# 85VAC_265VAC_6W_5V_SMPS_FLAYBACK.net
KiCad netlist of a schematic drawn in Altium Designer
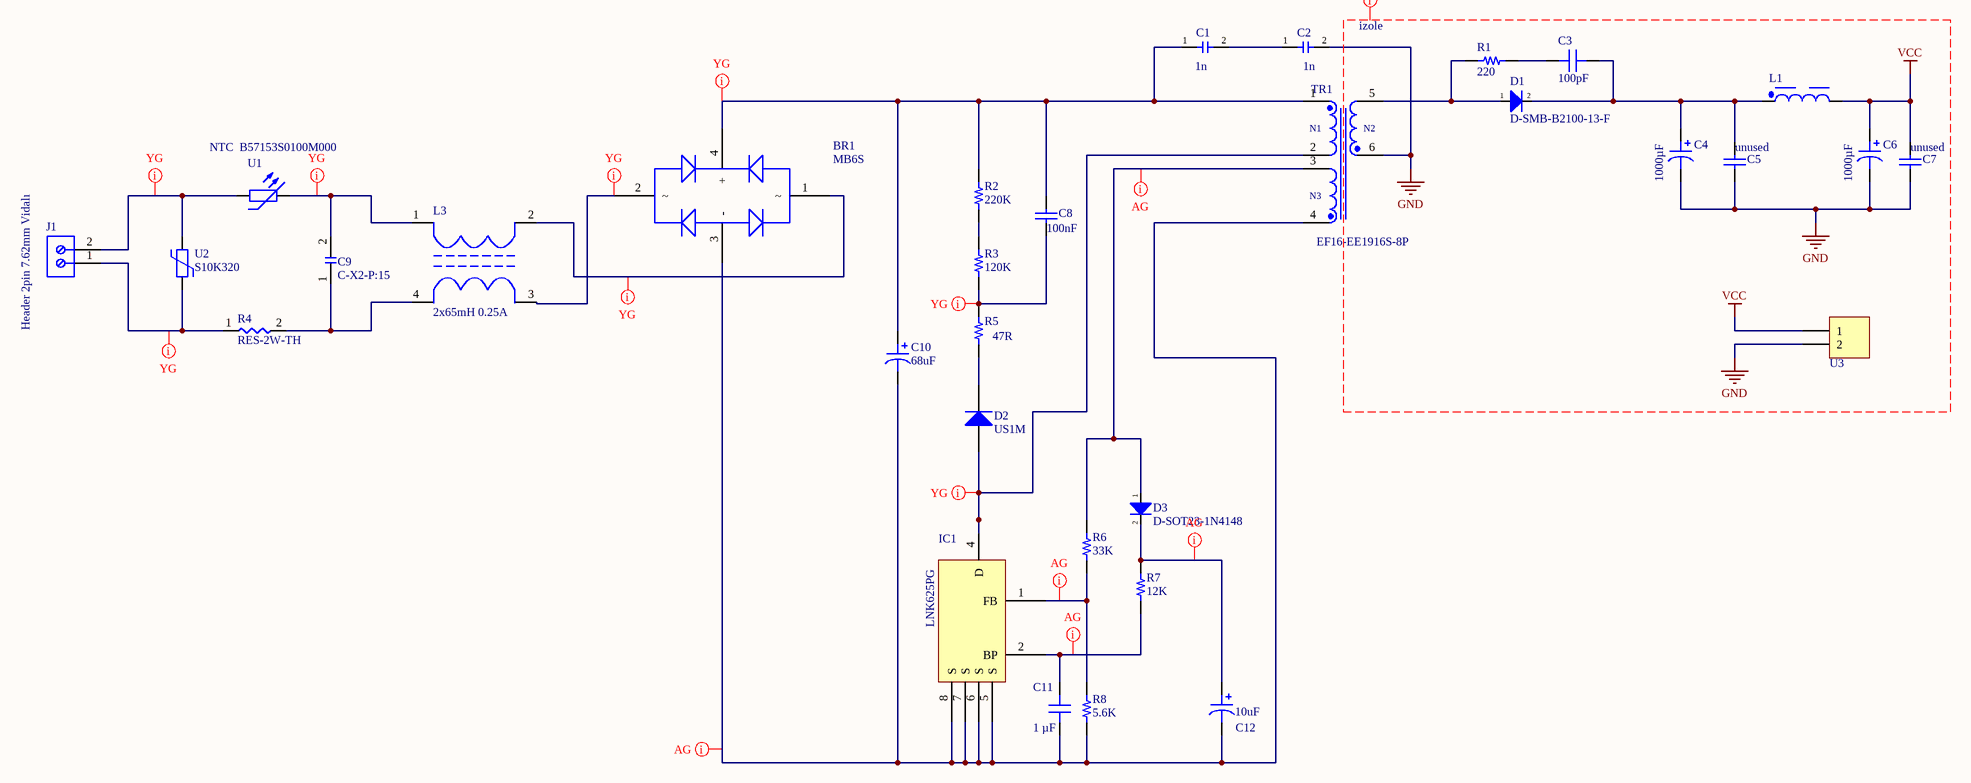
[diagram p0: 85VAC 265VAC 6W 5V SMPS FLAYBACK.SchDoc]

(export (version "E")
  (design (tool "Eeschema 10.0.6"))
  (components
    (comp (ref "BR1")
      (value "MB6S")
      (footprint "AltiumLive:TO269AA")
      (libsource (lib "AltiumLive") (part "MB6S"))
    )
    (comp (ref "C1")
      (value "1n")
      (footprint "AltiumLive:C-Y1-P:10")
      (libsource (lib "AltiumLive") (part "C-Y1-P{colon}10"))
    )
    (comp (ref "C2")
      (value "1n")
      (footprint "AltiumLive:C-Y1-P:10")
      (libsource (lib "AltiumLive") (part "C-Y1-P{colon}10"))
    )
    (comp (ref "C3")
      (value "100pF")
      (footprint "CAP 1206_3216 - 0.8MM")
      (description "CAP CER 1UF 25V X7R 1206")
      (fields (field (name "PART NUMBER") "CC1206KKX7R8BB105"))
      (libsource (lib "Celestial Altium Library - altium_library") (part "Capacitor"))
    )
    (comp (ref "C4")
      (value "~")
      (footprint "CAP TH ALUM ELEC D5.00mm S2.00mm H11.00mm")
      (description "CAP ALUM 1000UF 20% 25V RADIAL")
      (fields
        (field (name "PART NUMBER") "UKT1E4R7MDD")
        (field (name "CAPACITANCE") "1000µF")
        (field (name "MANUFACTURER") "Nichicon")
      )
      (libsource (lib "Celestial Altium Library - altium_library") (part "Polarised Capacitor"))
    )
    (comp (ref "C5")
      (value "unused")
      (footprint "WCAP-CSGP_1206_L3.2W1.6H0.8")
      (description "WCAP-CSGP Multilayer Ceramic Chip Capacitor, General Purpose, size 1206, NP0, 1nF, 25VDC")
      (fields
        (field (name "MANUFACTURER PART NUMBER") "885012008026")
        (field (name "MANUFACTURER") "Wurth Elektronik")
      )
      (libsource (lib "WE - Passive Components") (part "Capacitor_Non-Polarized"))
    )
    (comp (ref "C6")
      (value "~")
      (footprint "CAP TH ALUM ELEC D5.00mm S2.00mm H11.00mm")
      (description "CAP ALUM 1000UF 20% 25V RADIAL")
      (fields
        (field (name "PART NUMBER") "UKT1E4R7MDD")
        (field (name "CAPACITANCE") "1000µF")
        (field (name "MANUFACTURER") "Nichicon")
      )
      (libsource (lib "Celestial Altium Library - altium_library") (part "Polarised Capacitor"))
    )
    (comp (ref "C7")
      (value "unused")
      (footprint "WCAP-CSGP_1206_L3.2W1.6H0.8")
      (description "WCAP-CSGP Multilayer Ceramic Chip Capacitor, General Purpose, size 1206, NP0, 1nF, 25VDC")
      (fields
        (field (name "MANUFACTURER PART NUMBER") "885012008026")
        (field (name "MANUFACTURER") "Wurth Elektronik")
      )
      (libsource (lib "WE - Passive Components") (part "Capacitor_Non-Polarized"))
    )
    (comp (ref "C8")
      (value "100nF")
      (footprint "RCE7U2J333J5B1H03B")
      (description "490-8944-ND")
      (fields (field (name "PUBLISHER") "Altium Limited"))
      (libsource (lib "FlybackKutuphane") (part "C Seramik 100nF 1kV X7R 5mm"))
    )
    (comp (ref "C9")
      (value "C-X2-P:15")
      (footprint "AltiumLive:C-X2-P:15")
      (description "CAP-X2-R15-17.5x7.5")
      (libsource (lib "AltiumLive") (part "C-X2-P{colon}15"))
    )
    (comp (ref "C10")
      (value "68uF")
      (footprint "CAP TH ALUM ELEC D18.00mm S7.50mm H42.00mm")
      (description "CAP ALUM 68UF 20% 450V RADIAL")
      (fields (field (name "PART NUMBER") "EEU-EE2W680"))
      (libsource (lib "Celestial Altium Library - altium_library") (part "Polarised Capacitor"))
    )
    (comp (ref "C11")
      (value "1 µF")
      (footprint "CAP 1206_3216 - 0.8MM")
      (description "CAP CER 1UF 25V X7R 1206")
      (fields (field (name "PART NUMBER") "CC1206KKX7R8BB105"))
      (libsource (lib "Celestial Altium Library - altium_library") (part "Capacitor"))
    )
    (comp (ref "C12")
      (value "10uF")
      (footprint "CAP TH ALUM ELEC D6.30mm S2.50mm H6.00mm")
      (description "CAP ALUM 10UF 20% 50V RADIAL")
      (fields (field (name "PART NUMBER") "UMA1H100MDD"))
      (libsource (lib "Celestial Altium Library - altium_library") (part "Polarised Capacitor"))
    )
    (comp (ref "D1")
      (value "D-SMB-B2100-13-F")
      (footprint "AltiumLive:D-SMB-B2100-13-F")
      (libsource (lib "AltiumLive") (part "D-SMB-B2100-13-F"))
    )
    (comp (ref "D2")
      (value "US1M")
      (footprint "DO-214AA(SMB)")
      (description "SMA")
      (libsource (lib "FlybackKutuphane") (part "US1M"))
    )
    (comp (ref "D3")
      (value "D-SOT23-1N4148")
      (footprint "AltiumLive:SOT23-3")
      (libsource (lib "AltiumLive") (part "D-SOT23-1N4148"))
    )
    (comp (ref "IC1")
      (value "LNK625PG")
      (footprint "Altiumlive:PDIP-8C")
      (libsource (lib "AltiumLive") (part "LNK625PG"))
    )
    (comp (ref "J1")
      (value "Header 2pin 7.62mm Vidalı")
      (footprint "Header 2 Pin 7.62mm Vidalı")
      (description "691214410002")
      (fields (field (name "PART NUMBER") "691218410002") (field (name "PUBLISHER") "Wurth Elektronik"))
      (libsource (lib "FlybackKutuphane") (part "Header 2pin 7.62mm Vidalı"))
    )
    (comp (ref "L1")
      (value "1000uH, 0.25A")
      (footprint "WE-TI_5075")
      (description "WE-TI Radial Leaded Wire Wound Inductor, size 5075, 1000uH, 0.25A, 6Ohm")
      (fields
        (field (name "MANUFACTURER PART NUMBER") "7447462102")
        (field (name "MANUFACTURER") "Wurth Elektronik")
      )
      (libsource (lib "WE - Passive Components") (part "Inductor - 2"))
    )
    (comp (ref "L3")
      (value "2x65mH 0.25A")
      (footprint "AltiumLive:RN030923")
      (description "Line Filter RN030923")
      (libsource (lib "AltiumLive") (part "2x65mH 0.25A"))
    )
    (comp (ref "R1")
      (value "220")
      (footprint "RES 1206_3216")
      (description "RES 120K OHM 5% 1/4W 1206")
      (fields (field (name "PART NUMBER") "RMCF1206JT120K"))
      (libsource (lib "Celestial Altium Library - altium_library") (part "Resistor"))
    )
    (comp (ref "R2")
      (value "220K")
      (footprint "RES 1206_3216")
      (description "RES SMD 220K OHM 0.1% 1/4W 1206")
      (fields (field (name "PART NUMBER") "RT1206BRD07220KL"))
      (libsource (lib "Celestial Altium Library - altium_library") (part "Resistor"))
    )
    (comp (ref "R3")
      (value "120K")
      (footprint "RES 1206_3216")
      (description "RES 120K OHM 5% 1/4W 1206")
      (fields (field (name "PART NUMBER") "RMCF1206JT120K"))
      (libsource (lib "Celestial Altium Library - altium_library") (part "Resistor"))
    )
    (comp (ref "R4")
      (value "RES-2W-TH")
      (footprint "AltiumLive:RES-2W-TH")
      (libsource (lib "AltiumLive") (part "RES-2W-TH"))
    )
    (comp (ref "R5")
      (value "47R")
      (footprint "RES 1206_3216")
      (description "RES SMD 47 OHM 5% 1/4W 1206")
      (fields (field (name "PART NUMBER") "AC1206JR-0747RL"))
      (libsource (lib "Celestial Altium Library - altium_library") (part "Resistor"))
    )
    (comp (ref "R6")
      (value "33K")
      (footprint "RES 1206_3216")
      (description "RES 120K OHM 5% 1/4W 1206")
      (fields (field (name "PART NUMBER") "RMCF1206JT120K"))
      (libsource (lib "Celestial Altium Library - altium_library") (part "Resistor"))
    )
    (comp (ref "R7")
      (value "12K")
      (footprint "RES 1206_3216")
      (description "RES 12K OHM 5% 1/4W 1206")
      (fields (field (name "PART NUMBER") "RMCF1206JT120K"))
      (libsource (lib "Celestial Altium Library - altium_library") (part "Resistor"))
    )
    (comp (ref "R8")
      (value "5.6K")
      (footprint "RES 1206_3216")
      (description "RES 5.6K OHM 5% 1/4W 1206")
      (fields (field (name "PART NUMBER") "RMCF1206JT120K"))
      (libsource (lib "Celestial Altium Library - altium_library") (part "Resistor"))
    )
    (comp (ref "TR1")
      (value "EF16-EE1916S-8P")
      (footprint "AltiumLive:EF16-EE1916S-8P")
      (libsource (lib "AltiumLive") (part "EF16-EE1916S-8P"))
    )
    (comp (ref "U1")
      (value "NTC  B57153S0100M000")
      (footprint "NTC B57153S0100")
      (description "495-2076-ND")
      (fields (field (name "PUBLISHER") "Altium Limited"))
      (libsource (lib "FlybackKutuphane") (part "NTC 10R 2A 8.5mm"))
    )
    (comp (ref "U2")
      (value "S10K320")
      (footprint "Varistor630V")
      (fields (field (name "PUBLISHER") "Altium Limited"))
      (libsource (lib "FlybackKutuphane") (part "Varistor S10K320"))
    )
    (comp (ref "U3")
      (value "Terminal Blok 2 Pin 2.54mm")
      (footprint "Header 2pin 2.54mm Vidalı")
      (description "691210910002")
      (fields (field (name "PUBLISHER") "Altium Limited"))
      (libsource (lib "FlybackKutuphane") (part "Header 2 Pin 2.54mm Vidalı"))
    )
  )
  (nets
    (net (code "1") (name "GND") (class "Default")
      (node (ref "C2") (pin "2") (pintype "passive"))
      (node (ref "C4") (pin "2") (pinfunction "2_2") (pintype "passive"))
      (node (ref "C5") (pin "1") (pinfunction "1_1") (pintype "passive"))
      (node (ref "C6") (pin "2") (pinfunction "2_2") (pintype "passive"))
      (node (ref "C7") (pin "1") (pinfunction "1_1") (pintype "passive"))
      (node (ref "TR1") (pin "6") (pintype "passive"))
      (node (ref "U3") (pin "2") (pinfunction "2_2") (pintype "passive"))
    )
    (net (code "2") (name "Net-(BR1-+)") (class "Default")
      (node (ref "BR1") (pin "4") (pinfunction "+_4") (pintype "passive"))
      (node (ref "C1") (pin "1") (pintype "passive"))
      (node (ref "C10") (pin "1") (pinfunction "1_1") (pintype "passive"))
      (node (ref "C8") (pin "2") (pinfunction "2_2") (pintype "passive"))
      (node (ref "R2") (pin "2") (pinfunction "2_2") (pintype "passive"))
      (node (ref "TR1") (pin "1") (pintype "passive"))
    )
    (net (code "3") (name "Net-(BR1--)") (class "Default")
      (node (ref "BR1") (pin "3") (pinfunction "-_3") (pintype "passive"))
      (node (ref "C10") (pin "2") (pinfunction "2_2") (pintype "passive"))
      (node (ref "C11") (pin "1") (pinfunction "1_1") (pintype "passive"))
      (node (ref "C12") (pin "2") (pinfunction "2_2") (pintype "passive"))
      (node (ref "IC1") (pin "5") (pinfunction "S_5") (pintype "passive"))
      (node (ref "IC1") (pin "6") (pinfunction "S_6") (pintype "passive"))
      (node (ref "IC1") (pin "7") (pinfunction "S_7") (pintype "passive"))
      (node (ref "IC1") (pin "8") (pinfunction "S_8") (pintype "passive"))
      (node (ref "R8") (pin "1") (pinfunction "1_1") (pintype "passive"))
      (node (ref "TR1") (pin "4") (pintype "passive"))
    )
    (net (code "4") (name "Net-(BR1-~-Pad1)") (class "Default")
      (node (ref "BR1") (pin "1") (pinfunction "~_1") (pintype "passive"))
      (node (ref "L3") (pin "2") (pintype "passive"))
    )
    (net (code "5") (name "Net-(BR1-~-Pad2)") (class "Default")
      (node (ref "BR1") (pin "2") (pinfunction "~_2") (pintype "passive"))
      (node (ref "L3") (pin "3") (pintype "passive"))
    )
    (net (code "6") (name "Net-(C1-Pad2)") (class "Default")
      (node (ref "C1") (pin "2") (pintype "passive"))
      (node (ref "C2") (pin "1") (pintype "passive"))
    )
    (net (code "7") (name "Net-(C3-Pad1)") (class "Default")
      (node (ref "C3") (pin "1") (pinfunction "1_1") (pintype "passive"))
      (node (ref "C4") (pin "1") (pinfunction "1_1") (pintype "passive"))
      (node (ref "C5") (pin "2") (pinfunction "2_2") (pintype "passive"))
      (node (ref "D1") (pin "2") (pinfunction "A_2") (pintype "passive"))
      (node (ref "L1") (pin "1") (pinfunction "1_1") (pintype "passive"))
    )
    (net (code "8") (name "Net-(C3-Pad2)") (class "Default")
      (node (ref "C3") (pin "2") (pinfunction "2_2") (pintype "passive"))
      (node (ref "R1") (pin "1") (pinfunction "1_1") (pintype "passive"))
    )
    (net (code "9") (name "Net-(C8-Pad1)") (class "Default")
      (node (ref "C8") (pin "1") (pinfunction "1_1") (pintype "passive"))
      (node (ref "R3") (pin "1") (pinfunction "1_1") (pintype "passive"))
      (node (ref "R5") (pin "2") (pinfunction "2_2") (pintype "passive"))
    )
    (net (code "10") (name "Net-(C9-Pad1)") (class "Default")
      (node (ref "C9") (pin "1") (pintype "passive"))
      (node (ref "L3") (pin "4") (pintype "passive"))
      (node (ref "R4") (pin "2") (pintype "passive"))
    )
    (net (code "11") (name "Net-(C9-Pad2)") (class "Default")
      (node (ref "C9") (pin "2") (pintype "passive"))
      (node (ref "L3") (pin "1") (pintype "passive"))
      (node (ref "U1") (pin "2") (pinfunction "2_2") (pintype "passive"))
    )
    (net (code "12") (name "Net-(C12-Pad1)") (class "Default")
      (node (ref "C12") (pin "1") (pinfunction "1_1") (pintype "passive"))
      (node (ref "D3") (pin "2") (pinfunction "A_2") (pintype "passive"))
      (node (ref "R7") (pin "2") (pinfunction "2_2") (pintype "passive"))
    )
    (net (code "13") (name "Net-(D1-A-Pad1)") (class "Default")
      (node (ref "D1") (pin "1") (pinfunction "A_1") (pintype "passive"))
      (node (ref "R1") (pin "2") (pinfunction "2_2") (pintype "passive"))
      (node (ref "TR1") (pin "5") (pintype "passive"))
    )
    (net (code "14") (name "Net-(D2-A)") (class "Default")
      (node (ref "D2") (pin "1") (pinfunction "A_1") (pintype "passive"))
      (node (ref "IC1") (pin "4") (pinfunction "D_4") (pintype "passive"))
      (node (ref "TR1") (pin "2") (pinfunction "2_2") (pintype "passive"))
    )
    (net (code "15") (name "Net-(D2-K)") (class "Default")
      (node (ref "D2") (pin "2") (pinfunction "K_2") (pintype "passive"))
      (node (ref "R5") (pin "1") (pinfunction "1_1") (pintype "passive"))
    )
    (net (code "16") (name "Net-(D3-A-Pad1)") (class "Default")
      (node (ref "D3") (pin "1") (pinfunction "A_1") (pintype "passive"))
      (node (ref "R6") (pin "2") (pinfunction "2_2") (pintype "passive"))
      (node (ref "TR1") (pin "3") (pintype "passive"))
    )
    (net (code "17") (name "Net-(IC1-BP)") (class "Default")
      (node (ref "C11") (pin "2") (pinfunction "2_2") (pintype "passive"))
      (node (ref "IC1") (pin "2") (pinfunction "BP_2") (pintype "passive"))
      (node (ref "R7") (pin "1") (pinfunction "1_1") (pintype "passive"))
    )
    (net (code "18") (name "Net-(IC1-FB)") (class "Default")
      (node (ref "IC1") (pin "1") (pinfunction "FB_1") (pintype "passive"))
      (node (ref "R6") (pin "1") (pinfunction "1_1") (pintype "passive"))
      (node (ref "R8") (pin "2") (pinfunction "2_2") (pintype "passive"))
    )
    (net (code "19") (name "Net-(J1-Pad1)") (class "Default")
      (node (ref "J1") (pin "1") (pinfunction "1_1") (pintype "passive"))
      (node (ref "R4") (pin "1") (pintype "passive"))
      (node (ref "U2") (pin "2") (pinfunction "2_2") (pintype "passive"))
    )
    (net (code "20") (name "Net-(J1-Pad2)") (class "Default")
      (node (ref "J1") (pin "2") (pinfunction "2_2") (pintype "passive"))
      (node (ref "U1") (pin "1") (pinfunction "1_1") (pintype "passive"))
      (node (ref "U2") (pin "1") (pinfunction "1_1") (pintype "passive"))
    )
    (net (code "21") (name "Net-(R2-Pad1)") (class "Default")
      (node (ref "R2") (pin "1") (pinfunction "1_1") (pintype "passive"))
      (node (ref "R3") (pin "2") (pinfunction "2_2") (pintype "passive"))
    )
    (net (code "22") (name "VCC") (class "Default")
      (node (ref "C6") (pin "1") (pinfunction "1_1") (pintype "passive"))
      (node (ref "C7") (pin "2") (pinfunction "2_2") (pintype "passive"))
      (node (ref "L1") (pin "2") (pinfunction "2_2") (pintype "passive"))
      (node (ref "U3") (pin "1") (pinfunction "1_1") (pintype "passive"))
    )
  )
)
